# CUVET_DECTECT.net
KiCad netlist of a schematic drawn in Altium Designer
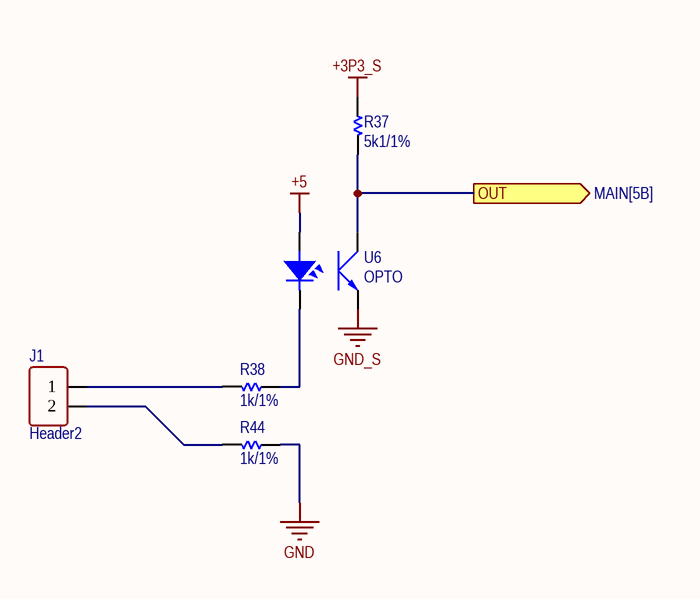
[diagram p0: CUVET_DECTECT.SchDoc]

(export (version "E")
  (design (tool "Eeschema 10.0.6"))
  (components
    (comp (ref "J1")
      (value "Header2")
      (footprint "XH2.54-2-DIP")
      (description "Connector 2")
      (fields
        (field (name "MANUFACTURER") "Würth Elektronik eiSos GmbH")
        (field (name "PARTNO") "613002143121")
        (field (name "CREATED BY") "Karrer Zheng")
      )
      (libsource (lib "Library") (part "Header2"))
    )
    (comp (ref "R37")
      (value "5k1/1%")
      (footprint "RES-SMD-0603")
      (description "ERJ-3EKF5101V")
      (fields
        (field (name "MANUFACTURER") "Generic Components")
        (field (name "PUBLISHER") "Altium Hobart Technology Centre")
      )
      (libsource (lib "Library") (part "Res-SMD"))
    )
    (comp (ref "R38")
      (value "1k/1%")
      (footprint "RES-SMD-0603")
      (description "ERJ-3EKF1001V")
      (fields
        (field (name "MANUFACTURER") "Generic Components")
        (field (name "PUBLISHER") "Altium Hobart Technology Centre")
      )
      (libsource (lib "Library") (part "Res-SMD"))
    )
    (comp (ref "R44")
      (value "1k/1%")
      (footprint "RES-SMD-0603")
      (description "ERJ-3EKF1001V")
      (fields
        (field (name "MANUFACTURER") "Generic Components")
        (field (name "PUBLISHER") "Altium Hobart Technology Centre")
      )
      (libsource (lib "Library") (part "Res-SMD"))
    )
    (comp (ref "U6")
      (value "OPTO")
      (footprint "EL3H7")
      (description "EL3H7(B)(TA)-VG")
      (libsource (lib "Library") (part "OPTO"))
    )
  )
  (nets
    (net (code "1") (name "+3P3_S") (class "Default")
      (node (ref "R37") (pin "1") (pinfunction "1_1") (pintype "passive"))
    )
    (net (code "2") (name "+5") (class "Default")
      (node (ref "U6") (pin "A") (pinfunction "A_A") (pintype "passive"))
    )
    (net (code "3") (name "/OUT") (class "Default")
      (node (ref "R37") (pin "2") (pinfunction "2_2") (pintype "passive"))
      (node (ref "U6") (pin "C") (pinfunction "C_C") (pintype "passive"))
    )
    (net (code "4") (name "GND") (class "Default")
      (node (ref "R44") (pin "2") (pinfunction "2_2") (pintype "passive"))
    )
    (net (code "5") (name "GND_S") (class "Default")
      (node (ref "U6") (pin "E") (pinfunction "E_E") (pintype "passive"))
    )
    (net (code "6") (name "Net-(J1-Pad1)") (class "Default")
      (node (ref "J1") (pin "1") (pinfunction "1_1") (pintype "passive"))
      (node (ref "R38") (pin "1") (pinfunction "1_1") (pintype "passive"))
    )
    (net (code "7") (name "Net-(J1-Pad2)") (class "Default")
      (node (ref "J1") (pin "2") (pinfunction "2_2") (pintype "passive"))
      (node (ref "R44") (pin "1") (pinfunction "1_1") (pintype "passive"))
    )
    (net (code "8") (name "Net-(R38-Pad2)") (class "Default")
      (node (ref "R38") (pin "2") (pinfunction "2_2") (pintype "passive"))
      (node (ref "U6") (pin "K") (pinfunction "K_K") (pintype "passive"))
    )
  )
)
